# SCH_NFC-business-card_2024-06-20.net
KiCad netlist of a schematic drawn in EasyEDA
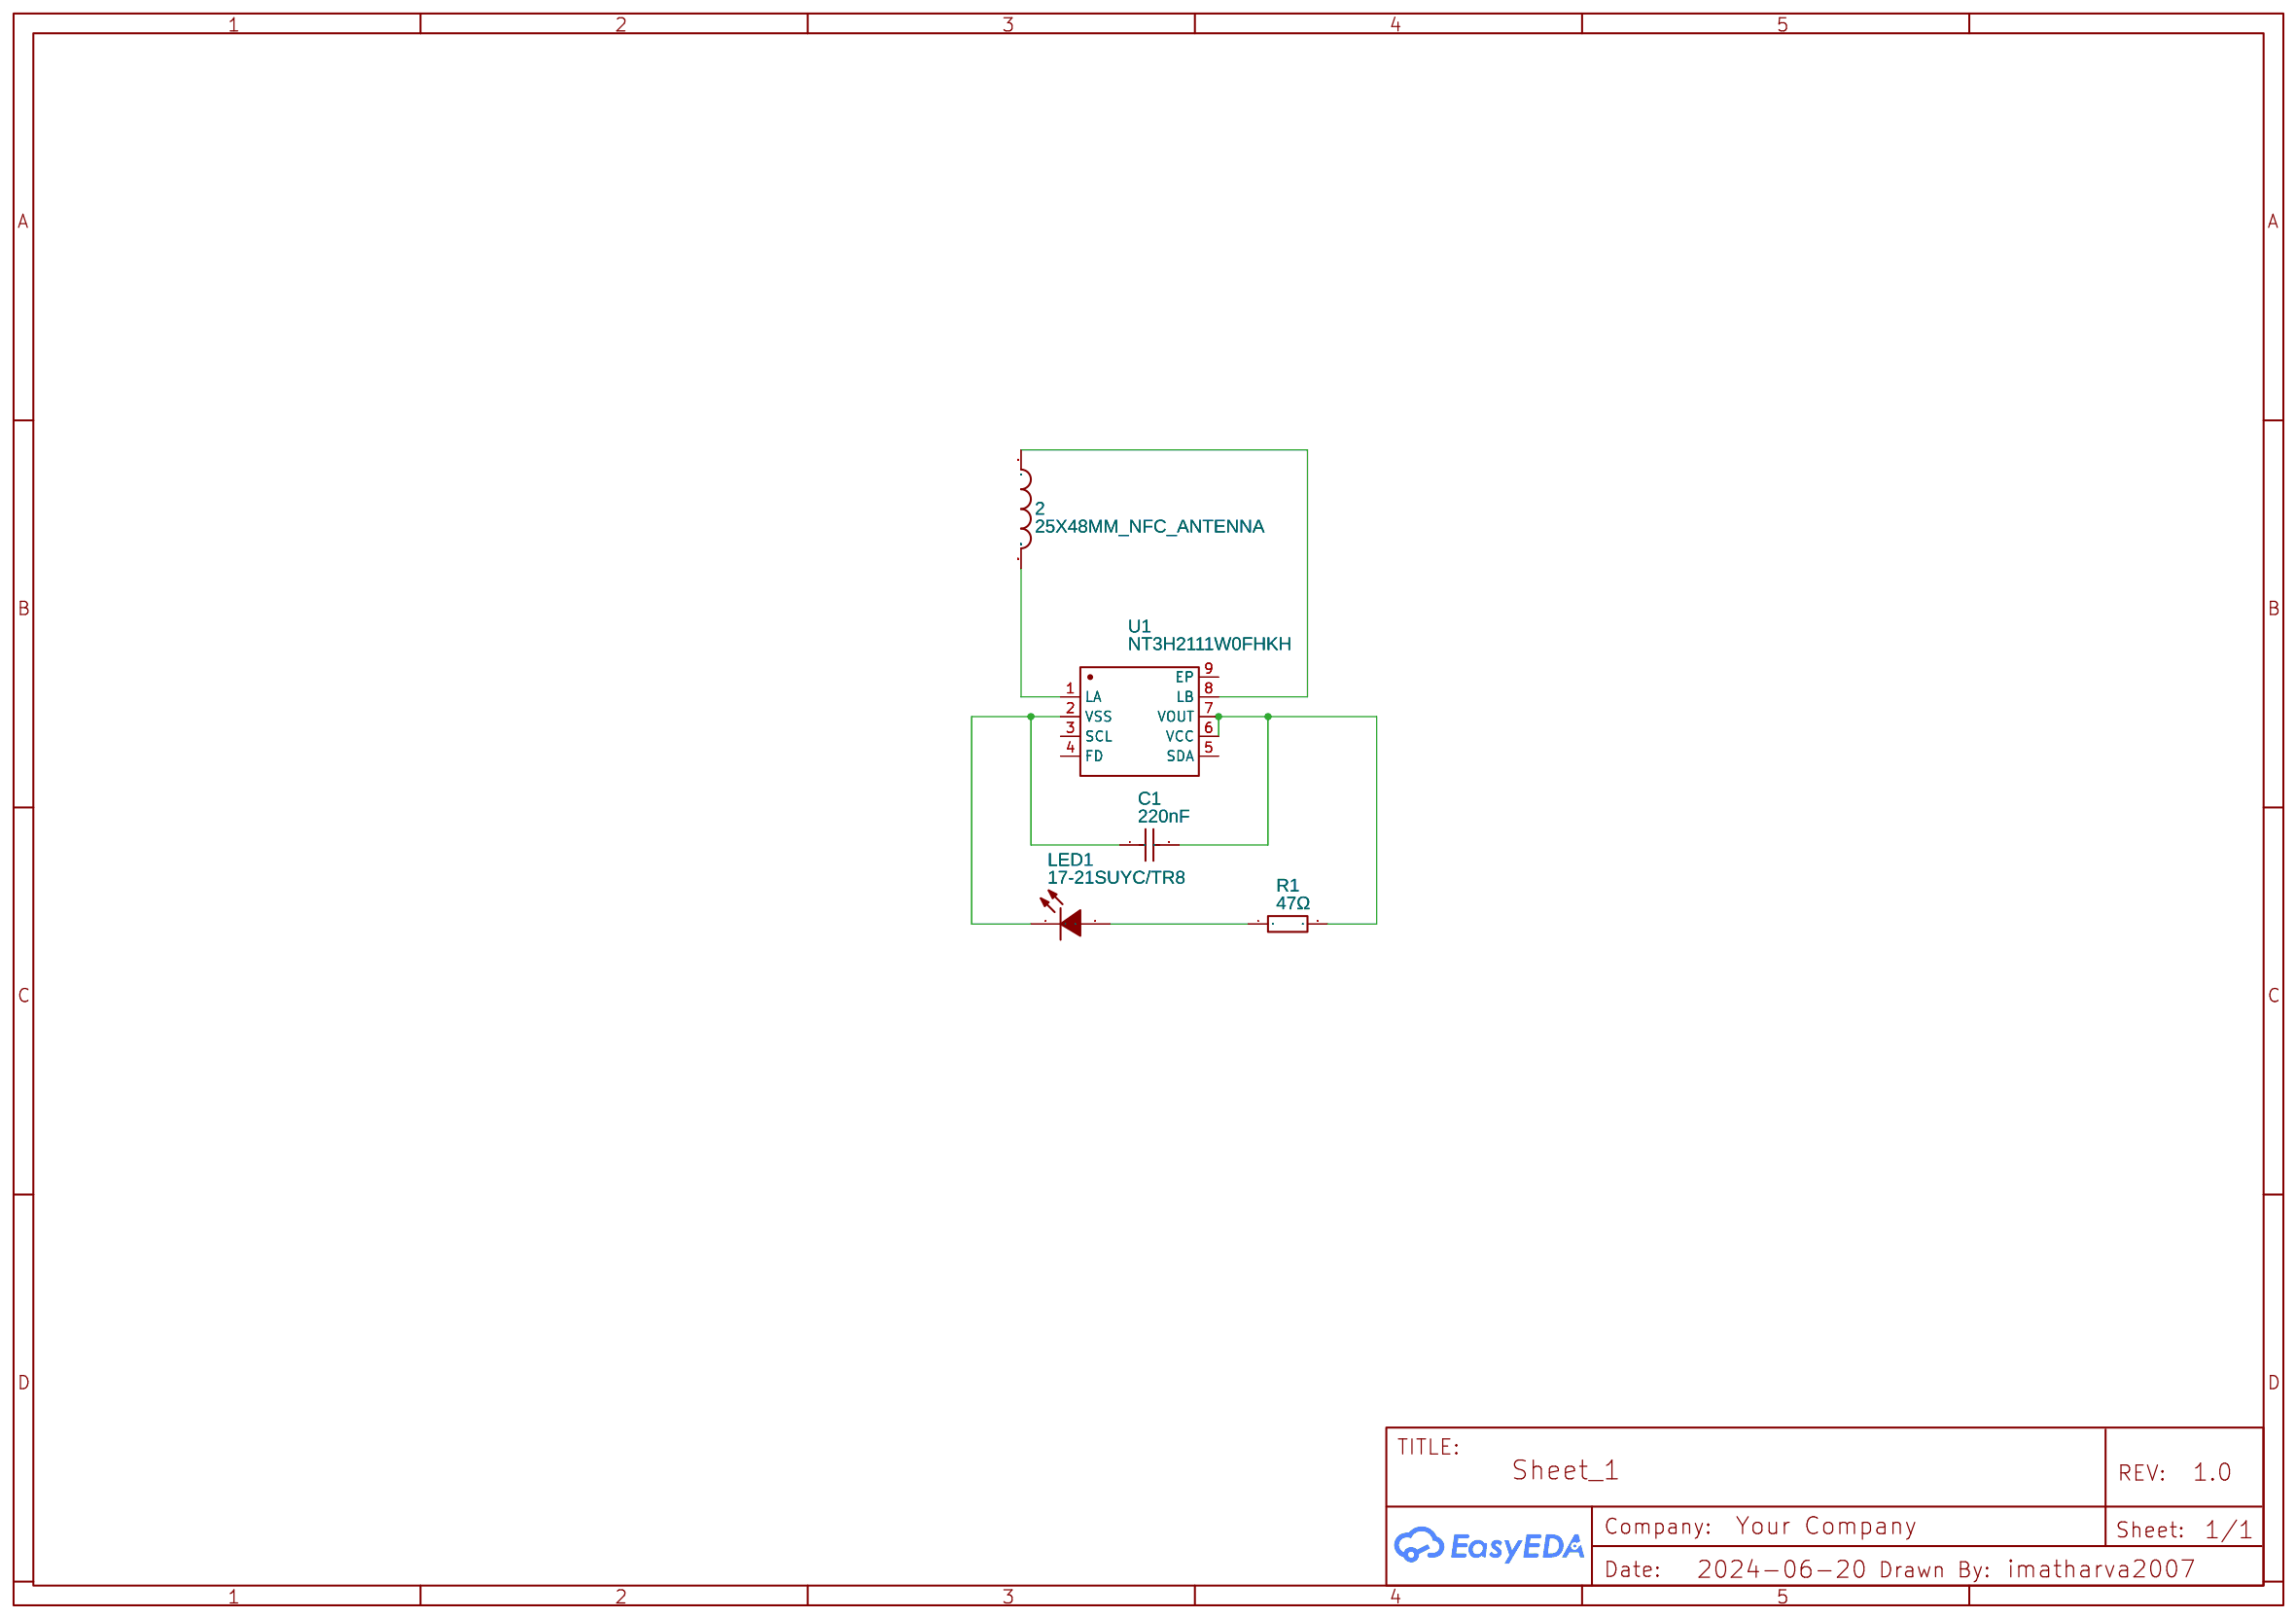
[diagram p0: schematic sheet]

(export (version "E")
  (design (tool "Eeschema 10.0.6"))
  (components
    (comp (ref "2") (value "25X48MM_NFC_ANTENNA") (libsource (lib "") (part "25X48MM_NFC_ANTENNA")))
    (comp (ref "C1")
      (value "220nF")
      (fields
        (field (name "Manufacturer Part") "CL10B224KA8NNNC")
        (field (name "Manufacturer") "SAMSUNG(三星)")
      )
      (libsource (lib "") (part "CL10B224KA8NNNC"))
    )
    (comp (ref "LED1")
      (value "17-21SUYC/TR8")
      (fields (field (name "Manufacturer Part") "KT-0805黄灯") (field (name "Manufacturer") "KENTO"))
      (libsource (lib "") (part "17-21SUYC/TR8"))
    )
    (comp (ref "R1")
      (value "47Ω")
      (fields
        (field (name "Manufacturer Part") "0603WAF470JT5E")
        (field (name "Manufacturer") "UNI-ROYAL(厚声)")
      )
      (libsource (lib "") (part "0603WAF470JT5E"))
    )
    (comp (ref "U1")
      (value "NT3H2111W0FHKH")
      (fields (field (name "Manufacturer") "NXP(恩智浦)"))
      (libsource (lib "") (part "NT3H2111W0FHKH"))
    )
  )
  (nets
    (net (code "1") (name "Net-(LED1-+)") (class "Default")
      (node (ref "LED1") (pin "1") (pinfunction "+_1") (pintype "unspecified"))
      (node (ref "R1") (pin "1") (pinfunction "1_1") (pintype "input"))
    )
    (net (code "2") (name "Net-(LED1--)") (class "Default")
      (node (ref "C1") (pin "1") (pinfunction "1_1") (pintype "input"))
      (node (ref "LED1") (pin "2") (pinfunction "-_2") (pintype "unspecified"))
      (node (ref "U1") (pin "2") (pinfunction "VSS_2") (pintype "unspecified"))
    )
    (net (code "3") (name "Net-(U1-LA)") (class "Default")
      (node (ref "2") (pin "P$2") (pinfunction "P$2_P$2") (pintype "bidirectional"))
      (node (ref "U1") (pin "1") (pinfunction "LA_1") (pintype "unspecified"))
    )
    (net (code "4") (name "Net-(U1-LB)") (class "Default")
      (node (ref "2") (pin "P$1") (pinfunction "P$1_P$1") (pintype "bidirectional"))
      (node (ref "U1") (pin "8") (pinfunction "LB_8") (pintype "unspecified"))
    )
    (net (code "5") (name "Net-(U1-VCC)") (class "Default")
      (node (ref "C1") (pin "2") (pinfunction "2_2") (pintype "input"))
      (node (ref "R1") (pin "2") (pinfunction "2_2") (pintype "input"))
      (node (ref "U1") (pin "6") (pinfunction "VCC_6") (pintype "unspecified"))
      (node (ref "U1") (pin "7") (pinfunction "VOUT_7") (pintype "unspecified"))
    )
    (net (code "6") (name "unconnected-(U1-EP-Pad9)") (class "Default")
      (node (ref "U1") (pin "9") (pinfunction "EP_9") (pintype "unspecified"))
    )
    (net (code "7") (name "unconnected-(U1-FD-Pad4)") (class "Default")
      (node (ref "U1") (pin "4") (pinfunction "FD_4") (pintype "unspecified"))
    )
    (net (code "8") (name "unconnected-(U1-SCL-Pad3)") (class "Default")
      (node (ref "U1") (pin "3") (pinfunction "SCL_3") (pintype "unspecified"))
    )
    (net (code "9") (name "unconnected-(U1-SDA-Pad5)") (class "Default")
      (node (ref "U1") (pin "5") (pinfunction "SDA_5") (pintype "unspecified"))
    )
  )
)
